# Dodobot.net
KiCad netlist of a schematic drawn in EAGLE
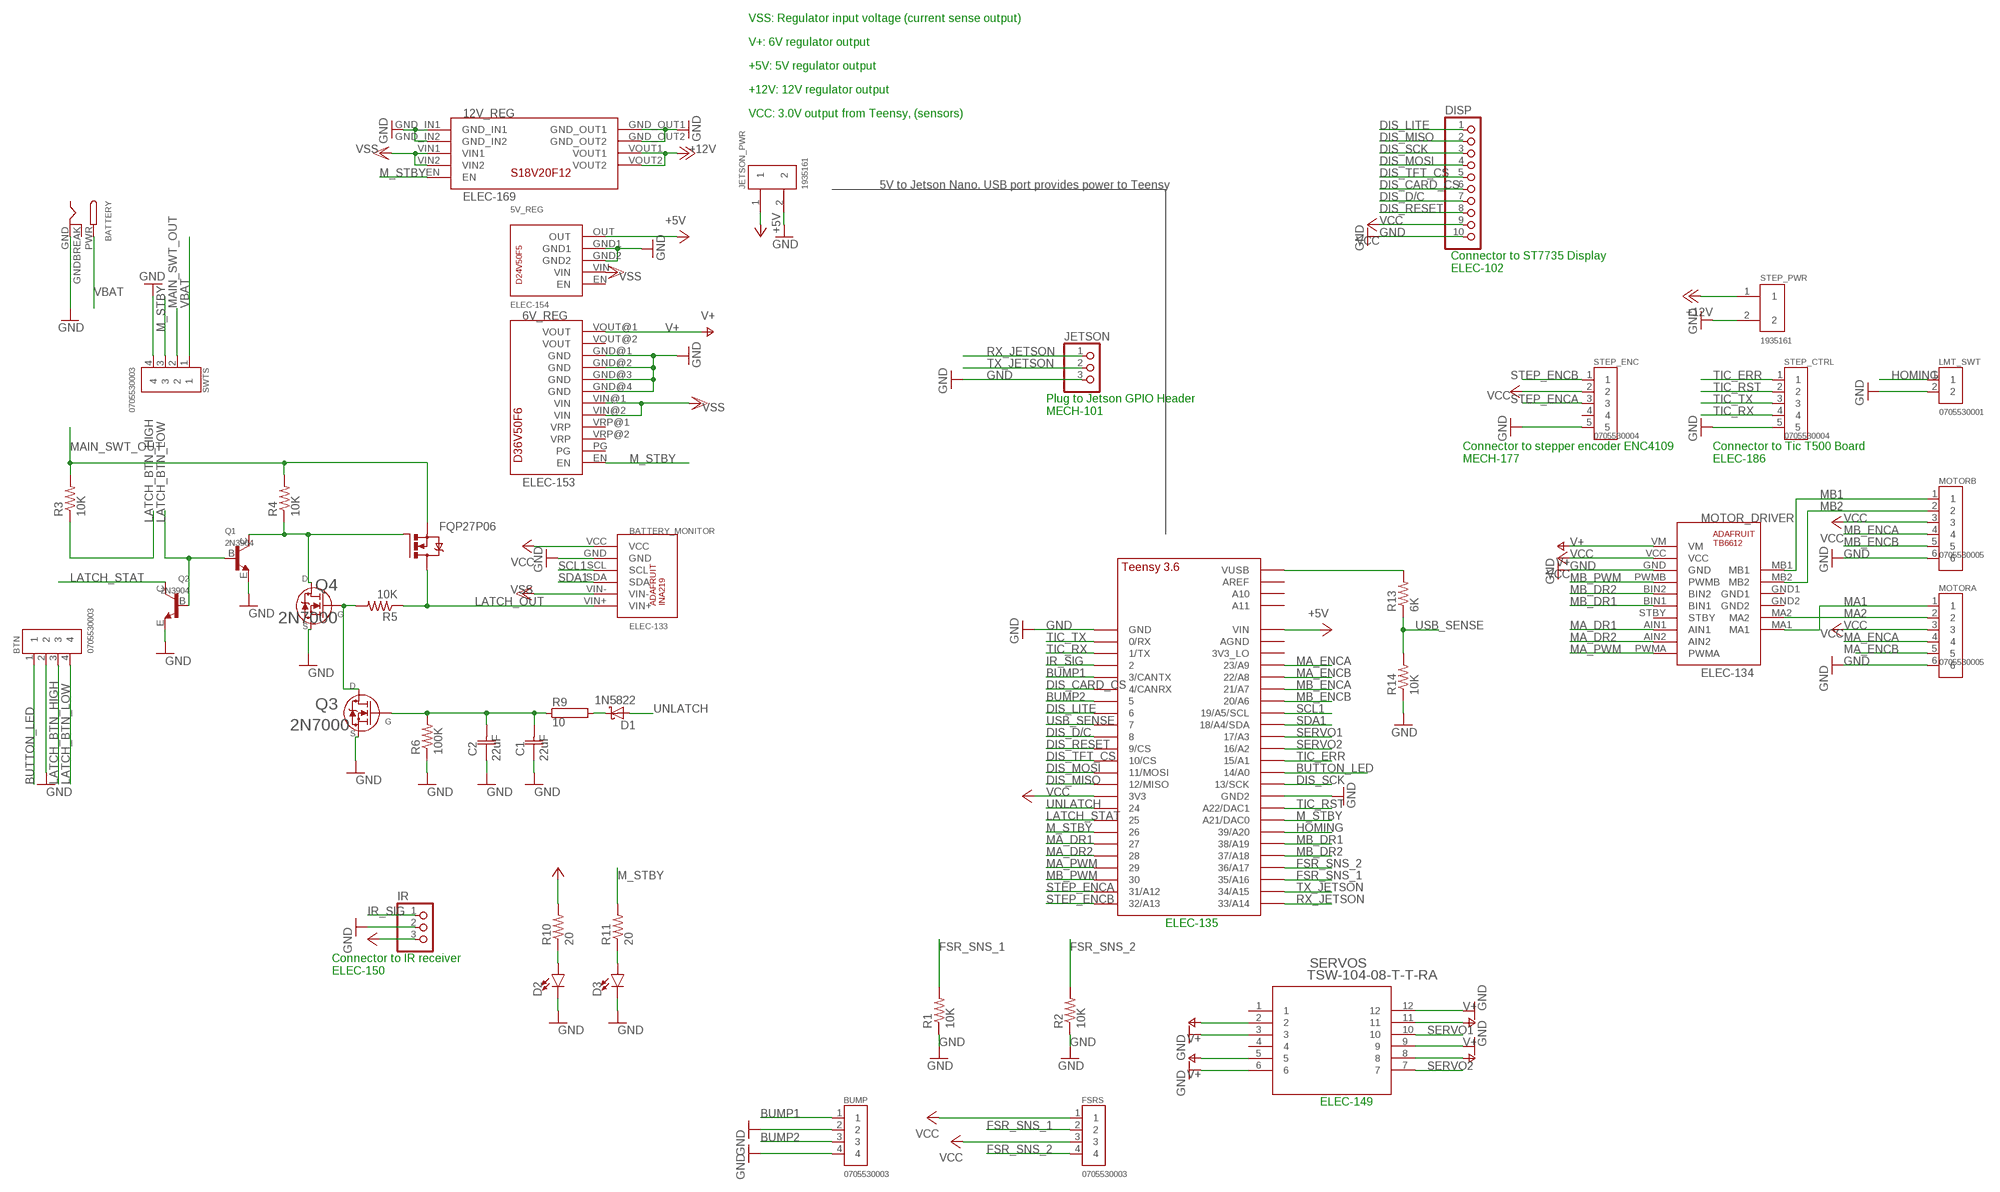
[diagram p0: schematic, sheet 1]

(export (version "E")
  (design (tool "Eeschema 10.0.6"))
  (components
    (comp (ref "5V_REG")
      (value "ELEC-154")
      (footprint "eagle-import:D24V50F5")
      (libsource (lib "eagle-import") (part "D24V50F5"))
    )
    (comp (ref "6V_REG")
      (value "ELEC-153")
      (footprint "eagle-import:D36V50FX")
      (libsource (lib "eagle-import") (part "D36V50FX"))
    )
    (comp (ref "12V_REG")
      (value "ELEC-169")
      (footprint "eagle-import:S18V20FX")
      (libsource (lib "eagle-import") (part "S18V20FX"))
    )
    (comp (ref "BATTERY")
      (value "DCBARRELPTH")
      (footprint "eagle-import:DCJACK_2MM_PTH")
      (libsource (lib "eagle-import") (part "DCBARRELPTH"))
    )
    (comp (ref "BATTERY_MONITOR")
      (value "ELEC-133")
      (footprint "eagle-import:INA219")
      (libsource (lib "eagle-import") (part "INA219"))
    )
    (comp (ref "BTN")
      (value "0705530003")
      (footprint "eagle-import:MOLEX_0705530003")
      (fields (field (name "DIGI-KEY_PART_NUMBER") "WM4902-ND") (field (name "MF") "Molex"))
      (libsource (lib "eagle-import") (part "0705530003"))
    )
    (comp (ref "BUMP")
      (value "0705530003")
      (footprint "eagle-import:MOLEX_0705530003")
      (fields (field (name "DIGI-KEY_PART_NUMBER") "WM4902-ND") (field (name "MF") "Molex"))
      (libsource (lib "eagle-import") (part "0705530003"))
    )
    (comp (ref "C1")
      (value "22uF")
      (footprint "eagle-import:CAP_R4525B")
      (fields (field (name "MANUFACTURER_PART_NUMBER") "FK24X5R0J226M"))
      (libsource (lib "eagle-import") (part "FK24X5R0J226M"))
    )
    (comp (ref "C2")
      (value "22uF")
      (footprint "eagle-import:CAP_R4525B")
      (fields (field (name "MANUFACTURER_PART_NUMBER") "FK24X5R0J226M"))
      (libsource (lib "eagle-import") (part "FK24X5R0J226M"))
    )
    (comp (ref "D1")
      (value "1N5822")
      (footprint "eagle-import:DIOAD2120W130L950D530P")
      (fields (field (name "DIGI-KEY_PART_NUMBER") "1N5822FSCT-ND") (field (name "MF") "ON Semiconductor"))
      (libsource (lib "eagle-import") (part "1N5822"))
    )
    (comp (ref "D2")
      (value "LED1206")
      (footprint "eagle-import:LED-1206")
      (libsource (lib "eagle-import") (part "LED1206"))
    )
    (comp (ref "D3")
      (value "LED1206")
      (footprint "eagle-import:LED-1206")
      (libsource (lib "eagle-import") (part "LED1206"))
    )
    (comp (ref "DISP")
      (value "PINHD-1X10")
      (footprint "eagle-import:1X10")
      (libsource (lib "eagle-import") (part "PINHD-1X10"))
    )
    (comp (ref "FQP27P06")
      (value "IRF530")
      (footprint "eagle-import:TO220BV")
      (fields (field (name "MF") "Vishay Siliconix"))
      (libsource (lib "eagle-import") (part "IRF530"))
    )
    (comp (ref "FSRS")
      (value "0705530003")
      (footprint "eagle-import:MOLEX_0705530003")
      (fields (field (name "DIGI-KEY_PART_NUMBER") "WM4902-ND") (field (name "MF") "Molex"))
      (libsource (lib "eagle-import") (part "0705530003"))
    )
    (comp (ref "IR")
      (value "PINHD-1X3")
      (footprint "eagle-import:1X03")
      (libsource (lib "eagle-import") (part "PINHD-1X3"))
    )
    (comp (ref "JETSON")
      (value "PINHD-1X3")
      (footprint "eagle-import:1X03")
      (libsource (lib "eagle-import") (part "PINHD-1X3"))
    )
    (comp (ref "JETSON_PWR")
      (value "1935161")
      (footprint "eagle-import:PHOENIX_1935161")
      (fields (field (name "DIGI-KEY_PART_NUMBER") "277-1667-ND") (field (name "MF") "Phoenix Contact"))
      (libsource (lib "eagle-import") (part "1935161"))
    )
    (comp (ref "LMT_SWT")
      (value "0705530001")
      (footprint "eagle-import:MOLEX_0705530001")
      (libsource (lib "eagle-import") (part "0705530001"))
    )
    (comp (ref "MOTORA")
      (value "0705530005")
      (footprint "eagle-import:MOLEX_0705530005")
      (libsource (lib "eagle-import") (part "0705530005"))
    )
    (comp (ref "MOTORB")
      (value "0705530005")
      (footprint "eagle-import:MOLEX_0705530005")
      (libsource (lib "eagle-import") (part "0705530005"))
    )
    (comp (ref "MOTOR_DRIVER")
      (value "ELEC-134")
      (footprint "eagle-import:ADAFRUIT_TB6612")
      (libsource (lib "eagle-import") (part "ADAFRUIT_TB6612"))
    )
    (comp (ref "Q1")
      (value "2N3904")
      (footprint "eagle-import:TO92")
      (libsource (lib "eagle-import") (part "2N3904"))
    )
    (comp (ref "Q2")
      (value "2N3904")
      (footprint "eagle-import:TO92")
      (libsource (lib "eagle-import") (part "2N3904"))
    )
    (comp (ref "Q3")
      (value "2N7000")
      (footprint "eagle-import:TO-92")
      (libsource (lib "eagle-import") (part "2N7000"))
    )
    (comp (ref "Q4")
      (value "2N7000")
      (footprint "eagle-import:TO-92")
      (libsource (lib "eagle-import") (part "2N7000"))
    )
    (comp (ref "R1")
      (value "10K")
      (footprint "eagle-import:RES_0805")
      (fields
        (field (name "DIGIKEY_PART_NUMBER") "541-0.0ATR-ND")
        (field (name "MANUFACTURER") "Vishay Dale")
        (field (name "MPN") "CRCW08050000Z0EA")
        (field (name "CREATED_BY") "PCBLayout.com")
      )
      (libsource (lib "eagle-import") (part "CRCW08050000Z0EA"))
    )
    (comp (ref "R2")
      (value "10K")
      (footprint "eagle-import:RES_0805")
      (fields
        (field (name "DIGIKEY_PART_NUMBER") "541-0.0ATR-ND")
        (field (name "MANUFACTURER") "Vishay Dale")
        (field (name "MPN") "CRCW08050000Z0EA")
        (field (name "CREATED_BY") "PCBLayout.com")
      )
      (libsource (lib "eagle-import") (part "CRCW08050000Z0EA"))
    )
    (comp (ref "R3")
      (value "10K")
      (footprint "eagle-import:RES_0805")
      (fields
        (field (name "DIGIKEY_PART_NUMBER") "541-0.0ATR-ND")
        (field (name "MANUFACTURER") "Vishay Dale")
        (field (name "MPN") "CRCW08050000Z0EA")
        (field (name "CREATED_BY") "PCBLayout.com")
      )
      (libsource (lib "eagle-import") (part "CRCW08050000Z0EA"))
    )
    (comp (ref "R4")
      (value "10K")
      (footprint "eagle-import:RES_0805")
      (fields
        (field (name "DIGIKEY_PART_NUMBER") "541-0.0ATR-ND")
        (field (name "MANUFACTURER") "Vishay Dale")
        (field (name "MPN") "CRCW08050000Z0EA")
        (field (name "CREATED_BY") "PCBLayout.com")
      )
      (libsource (lib "eagle-import") (part "CRCW08050000Z0EA"))
    )
    (comp (ref "R5")
      (value "10K")
      (footprint "eagle-import:RES_0805")
      (fields
        (field (name "DIGIKEY_PART_NUMBER") "541-0.0ATR-ND")
        (field (name "MANUFACTURER") "Vishay Dale")
        (field (name "MPN") "CRCW08050000Z0EA")
        (field (name "CREATED_BY") "PCBLayout.com")
      )
      (libsource (lib "eagle-import") (part "CRCW08050000Z0EA"))
    )
    (comp (ref "R6")
      (value "100K")
      (footprint "eagle-import:RES_0805")
      (fields
        (field (name "DIGIKEY_PART_NUMBER") "541-0.0ATR-ND")
        (field (name "MANUFACTURER") "Vishay Dale")
        (field (name "MPN") "CRCW08050000Z0EA")
        (field (name "CREATED_BY") "PCBLayout.com")
      )
      (libsource (lib "eagle-import") (part "CRCW08050000Z0EA"))
    )
    (comp (ref "R9")
      (value "10")
      (footprint "eagle-import:HPS58")
      (libsource (lib "eagle-import") (part "RHPS58"))
    )
    (comp (ref "R10")
      (value "20")
      (footprint "eagle-import:RES_1206")
      (fields
        (field (name "DIGIKEY_PART_NUMBER") "WSLP-.05TR-ND")
        (field (name "MANUFACTURER") "Vishay Dale")
        (field (name "MPN") "WSLP1206R0500FEA")
        (field (name "CREATED_BY") "PCBLayout.com")
      )
      (libsource (lib "eagle-import") (part "WSLP1206R0500FEA"))
    )
    (comp (ref "R11")
      (value "20")
      (footprint "eagle-import:RES_1206")
      (fields
        (field (name "DIGIKEY_PART_NUMBER") "WSLP-.05TR-ND")
        (field (name "MANUFACTURER") "Vishay Dale")
        (field (name "MPN") "WSLP1206R0500FEA")
        (field (name "CREATED_BY") "PCBLayout.com")
      )
      (libsource (lib "eagle-import") (part "WSLP1206R0500FEA"))
    )
    (comp (ref "R13")
      (value "6K")
      (footprint "eagle-import:RES_0805")
      (fields
        (field (name "DIGIKEY_PART_NUMBER") "541-0.0ATR-ND")
        (field (name "MANUFACTURER") "Vishay Dale")
        (field (name "MPN") "CRCW08050000Z0EA")
        (field (name "CREATED_BY") "PCBLayout.com")
      )
      (libsource (lib "eagle-import") (part "CRCW08050000Z0EA"))
    )
    (comp (ref "R14")
      (value "10K")
      (footprint "eagle-import:RES_0805")
      (fields
        (field (name "DIGIKEY_PART_NUMBER") "541-0.0ATR-ND")
        (field (name "MANUFACTURER") "Vishay Dale")
        (field (name "MPN") "CRCW08050000Z0EA")
        (field (name "CREATED_BY") "PCBLayout.com")
      )
      (libsource (lib "eagle-import") (part "CRCW08050000Z0EA"))
    )
    (comp (ref "SERVOS")
      (value "TSW-104-08-T-T-RA")
      (footprint "eagle-import:TSW-104-08-T-T-RA_SAI")
      (libsource (lib "eagle-import") (part "TSW-104-08-T-T-RA"))
    )
    (comp (ref "STEP_CTRL")
      (value "0705530004")
      (footprint "eagle-import:MOLEX_0705530004")
      (libsource (lib "eagle-import") (part "0705530004"))
    )
    (comp (ref "STEP_ENC")
      (value "0705530004")
      (footprint "eagle-import:MOLEX_0705530004")
      (libsource (lib "eagle-import") (part "0705530004"))
    )
    (comp (ref "STEP_PWR")
      (value "1935161")
      (footprint "eagle-import:PHOENIX_1935161")
      (fields (field (name "DIGI-KEY_PART_NUMBER") "277-1667-ND") (field (name "MF") "Phoenix Contact"))
      (libsource (lib "eagle-import") (part "1935161"))
    )
    (comp (ref "SWTS")
      (value "0705530003")
      (footprint "eagle-import:MOLEX_0705530003")
      (fields (field (name "DIGI-KEY_PART_NUMBER") "WM4902-ND") (field (name "MF") "Molex"))
      (libsource (lib "eagle-import") (part "0705530003"))
    )
    (comp (ref "U$1")
      (value "TEENSY_3.5/3.6_BASIC")
      (footprint "eagle-import:TEENSY_3.5_3.6_BASIC")
      (libsource (lib "eagle-import") (part "TEENSY_3.5/3.6_BASIC"))
    )
  )
  (nets
    (net (code "1") (name "+5V") (class "Default")
      (node (ref "5V_REG") (pin "OUT") (pinfunction "OUT_OUT") (pintype "bidirectional"))
      (node (ref "JETSON_PWR") (pin "1") (pinfunction "1_1") (pintype "passive"))
      (node (ref "U$1") (pin "VIN") (pinfunction "VIN_VIN") (pintype "bidirectional"))
    )
    (net (code "2") (name "+12V") (class "Default")
      (node (ref "12V_REG") (pin "VOUT1") (pinfunction "VOUT1_VOUT1") (pintype "bidirectional"))
      (node (ref "12V_REG") (pin "VOUT2") (pinfunction "VOUT2_VOUT2") (pintype "bidirectional"))
      (node (ref "STEP_PWR") (pin "1") (pinfunction "1_1") (pintype "passive"))
    )
    (net (code "3") (name "/BUMP1") (class "Default")
      (node (ref "BUMP") (pin "1") (pinfunction "1_1") (pintype "passive"))
      (node (ref "U$1") (pin "3/CANTX") (pinfunction "3/CANTX_3/CANTX") (pintype "bidirectional"))
    )
    (net (code "4") (name "/BUMP2") (class "Default")
      (node (ref "BUMP") (pin "3") (pinfunction "3_3") (pintype "passive"))
      (node (ref "U$1") (pin "5") (pinfunction "5_5") (pintype "bidirectional"))
    )
    (net (code "5") (name "/BUTTON_LED") (class "Default")
      (node (ref "BTN") (pin "1") (pinfunction "1_1") (pintype "passive"))
      (node (ref "U$1") (pin "14/A0") (pinfunction "14/A0_14/A0") (pintype "bidirectional"))
    )
    (net (code "6") (name "/DIS_CARD_CS") (class "Default")
      (node (ref "DISP") (pin "6") (pinfunction "6_6") (pintype "passive"))
      (node (ref "U$1") (pin "4/CANRX") (pinfunction "4/CANRX_4/CANRX") (pintype "bidirectional"))
    )
    (net (code "7") (name "/DIS_D{slash}C") (class "Default")
      (node (ref "DISP") (pin "7") (pinfunction "7_7") (pintype "passive"))
      (node (ref "U$1") (pin "8") (pinfunction "8_8") (pintype "bidirectional"))
    )
    (net (code "8") (name "/DIS_LITE") (class "Default")
      (node (ref "DISP") (pin "1") (pinfunction "1_1") (pintype "passive"))
      (node (ref "U$1") (pin "6") (pinfunction "6_6") (pintype "bidirectional"))
    )
    (net (code "9") (name "/DIS_MISO") (class "Default")
      (node (ref "DISP") (pin "2") (pinfunction "2_2") (pintype "passive"))
      (node (ref "U$1") (pin "12/MISO") (pinfunction "12/MISO_12/MISO") (pintype "bidirectional"))
    )
    (net (code "10") (name "/DIS_MOSI") (class "Default")
      (node (ref "DISP") (pin "4") (pinfunction "4_4") (pintype "passive"))
      (node (ref "U$1") (pin "11/MOSI") (pinfunction "11/MOSI_11/MOSI") (pintype "bidirectional"))
    )
    (net (code "11") (name "/DIS_RESET") (class "Default")
      (node (ref "DISP") (pin "8") (pinfunction "8_8") (pintype "passive"))
      (node (ref "U$1") (pin "9/CS") (pinfunction "9/CS_9/CS") (pintype "bidirectional"))
    )
    (net (code "12") (name "/DIS_SCK") (class "Default")
      (node (ref "DISP") (pin "3") (pinfunction "3_3") (pintype "passive"))
      (node (ref "U$1") (pin "13/SCK") (pinfunction "13/SCK_13/SCK") (pintype "bidirectional"))
    )
    (net (code "13") (name "/DIS_TFT_CS") (class "Default")
      (node (ref "DISP") (pin "5") (pinfunction "5_5") (pintype "passive"))
      (node (ref "U$1") (pin "10/CS") (pinfunction "10/CS_10/CS") (pintype "bidirectional"))
    )
    (net (code "14") (name "/FSR_SNS_1") (class "Default")
      (node (ref "FSRS") (pin "2") (pinfunction "2_2") (pintype "passive"))
      (node (ref "R1") (pin "2") (pinfunction "2_2") (pintype "passive"))
      (node (ref "U$1") (pin "35/A16") (pinfunction "35/A16_35/A16") (pintype "bidirectional"))
    )
    (net (code "15") (name "/FSR_SNS_2") (class "Default")
      (node (ref "FSRS") (pin "4") (pinfunction "4_4") (pintype "passive"))
      (node (ref "R2") (pin "2") (pinfunction "2_2") (pintype "passive"))
      (node (ref "U$1") (pin "36/A17") (pinfunction "36/A17_36/A17") (pintype "bidirectional"))
    )
    (net (code "16") (name "/GNDBREAK") (class "Default")
      (node (ref "BATTERY") (pin "GNDBREAK") (pinfunction "GNDBREAK_GNDBREAK") (pintype "power_in"))
    )
    (net (code "17") (name "/HOMING") (class "Default")
      (node (ref "LMT_SWT") (pin "1") (pinfunction "1_1") (pintype "passive"))
      (node (ref "U$1") (pin "39/A20") (pinfunction "39/A20_39/A20") (pintype "bidirectional"))
    )
    (net (code "18") (name "/IR_SIG") (class "Default")
      (node (ref "IR") (pin "1") (pinfunction "1_1") (pintype "passive"))
      (node (ref "U$1") (pin "2") (pinfunction "2_2") (pintype "bidirectional"))
    )
    (net (code "19") (name "/LATCH_BTN_HIGH") (class "Default")
      (node (ref "BTN") (pin "3") (pinfunction "3_3") (pintype "passive"))
      (node (ref "R3") (pin "1") (pinfunction "1_1") (pintype "passive"))
    )
    (net (code "20") (name "/LATCH_BTN_LOW") (class "Default")
      (node (ref "BTN") (pin "4") (pinfunction "4_4") (pintype "passive"))
      (node (ref "Q1") (pin "B") (pinfunction "B_B") (pintype "passive"))
      (node (ref "Q2") (pin "B") (pinfunction "B_B") (pintype "passive"))
    )
    (net (code "21") (name "/LATCH_OUT") (class "Default")
      (node (ref "BATTERY_MONITOR") (pin "VIN+") (pinfunction "VIN+_VIN+") (pintype "bidirectional"))
      (node (ref "FQP27P06") (pin "D") (pinfunction "D_D") (pintype "passive"))
      (node (ref "R5") (pin "1") (pinfunction "1_1") (pintype "passive"))
    )
    (net (code "22") (name "/LATCH_STAT") (class "Default")
      (node (ref "Q2") (pin "C") (pinfunction "C_C") (pintype "passive"))
      (node (ref "U$1") (pin "25") (pinfunction "25_25") (pintype "bidirectional"))
    )
    (net (code "23") (name "/MA1") (class "Default")
      (node (ref "MOTORA") (pin "1") (pinfunction "1_1") (pintype "passive"))
      (node (ref "MOTOR_DRIVER") (pin "MA1") (pinfunction "MA1_MA1") (pintype "bidirectional"))
    )
    (net (code "24") (name "/MA2") (class "Default")
      (node (ref "MOTORA") (pin "2") (pinfunction "2_2") (pintype "passive"))
      (node (ref "MOTOR_DRIVER") (pin "MA2") (pinfunction "MA2_MA2") (pintype "bidirectional"))
    )
    (net (code "25") (name "/MAIN_SWT_OUT") (class "Default")
      (node (ref "FQP27P06") (pin "S") (pinfunction "S_S") (pintype "passive"))
      (node (ref "R3") (pin "2") (pinfunction "2_2") (pintype "passive"))
      (node (ref "R4") (pin "2") (pinfunction "2_2") (pintype "passive"))
      (node (ref "SWTS") (pin "2") (pinfunction "2_2") (pintype "passive"))
    )
    (net (code "26") (name "/MA_DR1") (class "Default")
      (node (ref "MOTOR_DRIVER") (pin "AIN1") (pinfunction "AIN1_AIN1") (pintype "bidirectional"))
      (node (ref "U$1") (pin "27") (pinfunction "27_27") (pintype "bidirectional"))
    )
    (net (code "27") (name "/MA_DR2") (class "Default")
      (node (ref "MOTOR_DRIVER") (pin "AIN2") (pinfunction "AIN2_AIN2") (pintype "bidirectional"))
      (node (ref "U$1") (pin "28") (pinfunction "28_28") (pintype "bidirectional"))
    )
    (net (code "28") (name "/MA_ENCA") (class "Default")
      (node (ref "MOTORA") (pin "4") (pinfunction "4_4") (pintype "passive"))
      (node (ref "U$1") (pin "23/A9") (pinfunction "23/A9_23/A9") (pintype "bidirectional"))
    )
    (net (code "29") (name "/MA_ENCB") (class "Default")
      (node (ref "MOTORA") (pin "5") (pinfunction "5_5") (pintype "passive"))
      (node (ref "U$1") (pin "22/A8") (pinfunction "22/A8_22/A8") (pintype "bidirectional"))
    )
    (net (code "30") (name "/MA_PWM") (class "Default")
      (node (ref "MOTOR_DRIVER") (pin "PWMA") (pinfunction "PWMA_PWMA") (pintype "bidirectional"))
      (node (ref "U$1") (pin "29") (pinfunction "29_29") (pintype "bidirectional"))
    )
    (net (code "31") (name "/MB1") (class "Default")
      (node (ref "MOTORB") (pin "1") (pinfunction "1_1") (pintype "passive"))
      (node (ref "MOTOR_DRIVER") (pin "MB1") (pinfunction "MB1_MB1") (pintype "bidirectional"))
    )
    (net (code "32") (name "/MB2") (class "Default")
      (node (ref "MOTORB") (pin "2") (pinfunction "2_2") (pintype "passive"))
      (node (ref "MOTOR_DRIVER") (pin "MB2") (pinfunction "MB2_MB2") (pintype "bidirectional"))
    )
    (net (code "33") (name "/MB_DR1") (class "Default")
      (node (ref "MOTOR_DRIVER") (pin "BIN1") (pinfunction "BIN1_BIN1") (pintype "bidirectional"))
      (node (ref "U$1") (pin "38/A19") (pinfunction "38/A19_38/A19") (pintype "bidirectional"))
    )
    (net (code "34") (name "/MB_DR2") (class "Default")
      (node (ref "MOTOR_DRIVER") (pin "BIN2") (pinfunction "BIN2_BIN2") (pintype "bidirectional"))
      (node (ref "U$1") (pin "37/A18") (pinfunction "37/A18_37/A18") (pintype "bidirectional"))
    )
    (net (code "35") (name "/MB_ENCA") (class "Default")
      (node (ref "MOTORB") (pin "4") (pinfunction "4_4") (pintype "passive"))
      (node (ref "U$1") (pin "21/A7") (pinfunction "21/A7_21/A7") (pintype "bidirectional"))
    )
    (net (code "36") (name "/MB_ENCB") (class "Default")
      (node (ref "MOTORB") (pin "5") (pinfunction "5_5") (pintype "passive"))
      (node (ref "U$1") (pin "20/A6") (pinfunction "20/A6_20/A6") (pintype "bidirectional"))
    )
    (net (code "37") (name "/MB_PWM") (class "Default")
      (node (ref "MOTOR_DRIVER") (pin "PWMB") (pinfunction "PWMB_PWMB") (pintype "bidirectional"))
      (node (ref "U$1") (pin "30") (pinfunction "30_30") (pintype "bidirectional"))
    )
    (net (code "38") (name "/M_STBY") (class "Default")
      (node (ref "12V_REG") (pin "EN") (pinfunction "EN_EN") (pintype "bidirectional"))
      (node (ref "6V_REG") (pin "EN") (pinfunction "EN_EN") (pintype "bidirectional"))
      (node (ref "R11") (pin "2") (pinfunction "2_2") (pintype "passive"))
      (node (ref "SWTS") (pin "3") (pinfunction "3_3") (pintype "passive"))
      (node (ref "U$1") (pin "21/DAC0") (pinfunction "A21/DAC0_21/DAC0") (pintype "bidirectional"))
      (node (ref "U$1") (pin "26") (pinfunction "26_26") (pintype "bidirectional"))
    )
    (net (code "39") (name "/RX_JETSON") (class "Default")
      (node (ref "JETSON") (pin "1") (pinfunction "1_1") (pintype "passive"))
      (node (ref "U$1") (pin "33/A14") (pinfunction "33/A14_33/A14") (pintype "bidirectional"))
    )
    (net (code "40") (name "/SCL1") (class "Default")
      (node (ref "BATTERY_MONITOR") (pin "SCL") (pinfunction "SCL_SCL") (pintype "bidirectional"))
      (node (ref "U$1") (pin "19/A5/SCL") (pinfunction "19/A5/SCL_19/A5/SCL") (pintype "bidirectional"))
    )
    (net (code "41") (name "/SDA1") (class "Default")
      (node (ref "BATTERY_MONITOR") (pin "SDA") (pinfunction "SDA_SDA") (pintype "bidirectional"))
      (node (ref "U$1") (pin "18/A4/SDA") (pinfunction "18/A4/SDA_18/A4/SDA") (pintype "bidirectional"))
    )
    (net (code "42") (name "/SERVO1") (class "Default")
      (node (ref "SERVOS") (pin "10") (pinfunction "10_10") (pintype "passive"))
      (node (ref "U$1") (pin "17/A3") (pinfunction "17/A3_17/A3") (pintype "bidirectional"))
    )
    (net (code "43") (name "/SERVO2") (class "Default")
      (node (ref "SERVOS") (pin "7") (pinfunction "7_7") (pintype "passive"))
      (node (ref "U$1") (pin "16/A2") (pinfunction "16/A2_16/A2") (pintype "bidirectional"))
    )
    (net (code "44") (name "/STEP_ENCA") (class "Default")
      (node (ref "STEP_ENC") (pin "3") (pinfunction "3_3") (pintype "passive"))
      (node (ref "U$1") (pin "31/A12") (pinfunction "31/A12_31/A12") (pintype "bidirectional"))
    )
    (net (code "45") (name "/STEP_ENCB") (class "Default")
      (node (ref "STEP_ENC") (pin "1") (pinfunction "1_1") (pintype "passive"))
      (node (ref "U$1") (pin "32/A13") (pinfunction "32/A13_32/A13") (pintype "bidirectional"))
    )
    (net (code "46") (name "/TIC_ERR") (class "Default")
      (node (ref "STEP_CTRL") (pin "1") (pinfunction "1_1") (pintype "passive"))
      (node (ref "U$1") (pin "15/A1") (pinfunction "15/A1_15/A1") (pintype "bidirectional"))
    )
    (net (code "47") (name "/TIC_RST") (class "Default")
      (node (ref "STEP_CTRL") (pin "2") (pinfunction "2_2") (pintype "passive"))
      (node (ref "U$1") (pin "A22/DAC1") (pinfunction "A22/DAC1_A22/DAC1") (pintype "bidirectional"))
    )
    (net (code "48") (name "/TIC_RX") (class "Default")
      (node (ref "STEP_CTRL") (pin "4") (pinfunction "4_4") (pintype "passive"))
      (node (ref "U$1") (pin "1/TX") (pinfunction "1/TX_1/TX") (pintype "bidirectional"))
    )
    (net (code "49") (name "/TIC_TX") (class "Default")
      (node (ref "STEP_CTRL") (pin "3") (pinfunction "3_3") (pintype "passive"))
      (node (ref "U$1") (pin "0/RX") (pinfunction "0/RX_0/RX") (pintype "bidirectional"))
    )
    (net (code "50") (name "/TX_JETSON") (class "Default")
      (node (ref "JETSON") (pin "2") (pinfunction "2_2") (pintype "passive"))
      (node (ref "U$1") (pin "34/A15") (pinfunction "34/A15_34/A15") (pintype "bidirectional"))
    )
    (net (code "51") (name "/UNLATCH") (class "Default")
      (node (ref "D1") (pin "A") (pinfunction "A_A") (pintype "passive"))
      (node (ref "U$1") (pin "24") (pinfunction "24_24") (pintype "bidirectional"))
    )
    (net (code "52") (name "/USB_SENSE") (class "Default")
      (node (ref "R13") (pin "1") (pinfunction "1_1") (pintype "passive"))
      (node (ref "R14") (pin "2") (pinfunction "2_2") (pintype "passive"))
      (node (ref "U$1") (pin "7") (pinfunction "7_7") (pintype "bidirectional"))
    )
    (net (code "53") (name "/VBAT") (class "Default")
      (node (ref "BATTERY") (pin "PWR") (pinfunction "PWR_PWR") (pintype "power_in"))
      (node (ref "SWTS") (pin "1") (pinfunction "1_1") (pintype "passive"))
    )
    (net (code "54") (name "GND") (class "Default")
      (node (ref "12V_REG") (pin "GND_IN1") (pinfunction "GND_IN1_GND_IN1") (pintype "bidirectional"))
      (node (ref "12V_REG") (pin "GND_IN2") (pinfunction "GND_IN2_GND_IN2") (pintype "bidirectional"))
      (node (ref "12V_REG") (pin "GND_OUT1") (pinfunction "GND_OUT1_GND_OUT1") (pintype "bidirectional"))
      (node (ref "12V_REG") (pin "GND_OUT2") (pinfunction "GND_OUT2_GND_OUT2") (pintype "bidirectional"))
      (node (ref "5V_REG") (pin "GND1") (pinfunction "GND1_GND1") (pintype "bidirectional"))
      (node (ref "5V_REG") (pin "GND2") (pinfunction "GND2_GND2") (pintype "bidirectional"))
      (node (ref "6V_REG") (pin "GND@1") (pinfunction "GND_GND@1") (pintype "bidirectional"))
      (node (ref "6V_REG") (pin "GND@2") (pinfunction "GND_GND@2") (pintype "bidirectional"))
      (node (ref "6V_REG") (pin "GND@3") (pinfunction "GND_GND@3") (pintype "bidirectional"))
      (node (ref "6V_REG") (pin "GND@4") (pinfunction "GND_GND@4") (pintype "bidirectional"))
      (node (ref "BATTERY") (pin "GND") (pinfunction "GND_GND") (pintype "power_in"))
      (node (ref "BATTERY_MONITOR") (pin "GND") (pinfunction "GND_GND") (pintype "bidirectional"))
      (node (ref "BTN") (pin "2") (pinfunction "2_2") (pintype "passive"))
      (node (ref "BUMP") (pin "2") (pinfunction "2_2") (pintype "passive"))
      (node (ref "BUMP") (pin "4") (pinfunction "4_4") (pintype "passive"))
      (node (ref "C1") (pin "1") (pinfunction "1_1") (pintype "passive"))
      (node (ref "C2") (pin "1") (pinfunction "1_1") (pintype "passive"))
      (node (ref "D2") (pin "C") (pinfunction "C_C") (pintype "passive"))
      (node (ref "D3") (pin "C") (pinfunction "C_C") (pintype "passive"))
      (node (ref "DISP") (pin "10") (pinfunction "10_10") (pintype "passive"))
      (node (ref "IR") (pin "2") (pinfunction "2_2") (pintype "passive"))
      (node (ref "JETSON") (pin "3") (pinfunction "3_3") (pintype "passive"))
      (node (ref "JETSON_PWR") (pin "2") (pinfunction "2_2") (pintype "passive"))
      (node (ref "LMT_SWT") (pin "2") (pinfunction "2_2") (pintype "passive"))
      (node (ref "MOTORA") (pin "6") (pinfunction "6_6") (pintype "passive"))
      (node (ref "MOTORB") (pin "6") (pinfunction "6_6") (pintype "passive"))
      (node (ref "MOTOR_DRIVER") (pin "GND") (pinfunction "GND_GND") (pintype "bidirectional"))
      (node (ref "Q1") (pin "E") (pinfunction "E_E") (pintype "passive"))
      (node (ref "Q2") (pin "E") (pinfunction "E_E") (pintype "passive"))
      (node (ref "Q3") (pin "1") (pinfunction "3_1") (pintype "passive"))
      (node (ref "Q4") (pin "1") (pinfunction "3_1") (pintype "passive"))
      (node (ref "R1") (pin "1") (pinfunction "1_1") (pintype "passive"))
      (node (ref "R14") (pin "1") (pinfunction "1_1") (pintype "passive"))
      (node (ref "R2") (pin "1") (pinfunction "1_1") (pintype "passive"))
      (node (ref "R6") (pin "1") (pinfunction "1_1") (pintype "passive"))
      (node (ref "SERVOS") (pin "12") (pinfunction "12_12") (pintype "passive"))
      (node (ref "SERVOS") (pin "3") (pinfunction "3_3") (pintype "passive"))
      (node (ref "SERVOS") (pin "6") (pinfunction "6_6") (pintype "passive"))
      (node (ref "SERVOS") (pin "9") (pinfunction "9_9") (pintype "passive"))
      (node (ref "STEP_CTRL") (pin "5") (pinfunction "5_5") (pintype "passive"))
      (node (ref "STEP_ENC") (pin "5") (pinfunction "5_5") (pintype "passive"))
      (node (ref "STEP_PWR") (pin "2") (pinfunction "2_2") (pintype "passive"))
      (node (ref "SWTS") (pin "4") (pinfunction "4_4") (pintype "passive"))
      (node (ref "U$1") (pin "GND") (pinfunction "GND_GND") (pintype "bidirectional"))
      (node (ref "U$1") (pin "GND2") (pinfunction "GND2_GND2") (pintype "bidirectional"))
    )
    (net (code "55") (name "Net-(D1-PadC)") (class "Default")
      (node (ref "D1") (pin "C") (pinfunction "C_C") (pintype "passive"))
      (node (ref "R9") (pin "2") (pinfunction "2_2") (pintype "passive"))
    )
    (net (code "56") (name "Net-(D2-PadA)") (class "Default")
      (node (ref "D2") (pin "A") (pinfunction "A_A") (pintype "passive"))
      (node (ref "R10") (pin "1") (pinfunction "1_1") (pintype "passive"))
    )
    (net (code "57") (name "Net-(D3-PadA)") (class "Default")
      (node (ref "D3") (pin "A") (pinfunction "A_A") (pintype "passive"))
      (node (ref "R11") (pin "1") (pinfunction "1_1") (pintype "passive"))
    )
    (net (code "58") (name "Net-(Q3-1)") (class "Default")
      (node (ref "C1") (pin "2") (pinfunction "2_2") (pintype "passive"))
      (node (ref "C2") (pin "2") (pinfunction "2_2") (pintype "passive"))
      (node (ref "Q3") (pin "2") (pinfunction "1_2") (pintype "passive"))
      (node (ref "R6") (pin "2") (pinfunction "2_2") (pintype "passive"))
      (node (ref "R9") (pin "1") (pinfunction "1_1") (pintype "passive"))
    )
    (net (code "59") (name "Net-(Q3-2)") (class "Default")
      (node (ref "Q3") (pin "3") (pinfunction "2_3") (pintype "passive"))
      (node (ref "Q4") (pin "2") (pinfunction "1_2") (pintype "passive"))
      (node (ref "R5") (pin "2") (pinfunction "2_2") (pintype "passive"))
    )
    (net (code "60") (name "Net-(Q4-2)") (class "Default")
      (node (ref "FQP27P06") (pin "G") (pinfunction "G_G") (pintype "passive"))
      (node (ref "Q1") (pin "C") (pinfunction "C_C") (pintype "passive"))
      (node (ref "Q4") (pin "3") (pinfunction "2_3") (pintype "passive"))
      (node (ref "R4") (pin "1") (pinfunction "1_1") (pintype "passive"))
    )
    (net (code "61") (name "Net-(R13-Pad2)") (class "Default")
      (node (ref "R13") (pin "2") (pinfunction "2_2") (pintype "passive"))
      (node (ref "U$1") (pin "VUSB") (pinfunction "VUSB_VUSB") (pintype "bidirectional"))
    )
    (net (code "62") (name "V+") (class "Default")
      (node (ref "6V_REG") (pin "VOUT@1") (pinfunction "VOUT_VOUT@1") (pintype "bidirectional"))
      (node (ref "MOTOR_DRIVER") (pin "VM") (pinfunction "VM_VM") (pintype "bidirectional"))
      (node (ref "SERVOS") (pin "11") (pinfunction "11_11") (pintype "passive"))
      (node (ref "SERVOS") (pin "2") (pinfunction "2_2") (pintype "passive"))
      (node (ref "SERVOS") (pin "5") (pinfunction "5_5") (pintype "passive"))
      (node (ref "SERVOS") (pin "8") (pinfunction "8_8") (pintype "passive"))
    )
    (net (code "63") (name "VCC") (class "Default")
      (node (ref "BATTERY_MONITOR") (pin "VCC") (pinfunction "VCC_VCC") (pintype "bidirectional"))
      (node (ref "DISP") (pin "9") (pinfunction "9_9") (pintype "passive"))
      (node (ref "FSRS") (pin "1") (pinfunction "1_1") (pintype "passive"))
      (node (ref "FSRS") (pin "3") (pinfunction "3_3") (pintype "passive"))
      (node (ref "IR") (pin "3") (pinfunction "3_3") (pintype "passive"))
      (node (ref "MOTORA") (pin "3") (pinfunction "3_3") (pintype "passive"))
      (node (ref "MOTORB") (pin "3") (pinfunction "3_3") (pintype "passive"))
      (node (ref "MOTOR_DRIVER") (pin "VCC") (pinfunction "VCC_VCC") (pintype "bidirectional"))
      (node (ref "R10") (pin "2") (pinfunction "2_2") (pintype "passive"))
      (node (ref "STEP_ENC") (pin "2") (pinfunction "2_2") (pintype "passive"))
      (node (ref "U$1") (pin "3V3") (pinfunction "3V3_3V3") (pintype "bidirectional"))
    )
    (net (code "64") (name "VSS") (class "Default")
      (node (ref "12V_REG") (pin "VIN1") (pinfunction "VIN1_VIN1") (pintype "bidirectional"))
      (node (ref "12V_REG") (pin "VIN2") (pinfunction "VIN2_VIN2") (pintype "bidirectional"))
      (node (ref "5V_REG") (pin "VIN") (pinfunction "VIN_VIN") (pintype "bidirectional"))
      (node (ref "6V_REG") (pin "VIN@1") (pinfunction "VIN_VIN@1") (pintype "bidirectional"))
      (node (ref "6V_REG") (pin "VIN@2") (pinfunction "VIN_VIN@2") (pintype "bidirectional"))
      (node (ref "BATTERY_MONITOR") (pin "VIN-") (pinfunction "VIN-_VIN-") (pintype "bidirectional"))
    )
    (net (code "65") (name "unconnected-(5V_REG-PadEN)") (class "Default")
      (node (ref "5V_REG") (pin "EN") (pinfunction "EN_EN") (pintype "bidirectional"))
    )
    (net (code "66") (name "unconnected-(6V_REG-PadPG)") (class "Default")
      (node (ref "6V_REG") (pin "PG") (pinfunction "PG_PG") (pintype "bidirectional"))
    )
    (net (code "67") (name "unconnected-(6V_REG-VOUT-PadVOUT@2)") (class "Default")
      (node (ref "6V_REG") (pin "VOUT@2") (pinfunction "VOUT_VOUT@2") (pintype "bidirectional"))
    )
    (net (code "68") (name "unconnected-(6V_REG-VRP-PadVRP@1)") (class "Default")
      (node (ref "6V_REG") (pin "VRP@1") (pinfunction "VRP_VRP@1") (pintype "bidirectional"))
    )
    (net (code "69") (name "unconnected-(6V_REG-VRP-PadVRP@2)") (class "Default")
      (node (ref "6V_REG") (pin "VRP@2") (pinfunction "VRP_VRP@2") (pintype "bidirectional"))
    )
    (net (code "70") (name "unconnected-(MOTOR_DRIVER-PadGND1)") (class "Default")
      (node (ref "MOTOR_DRIVER") (pin "GND1") (pinfunction "GND1_GND1") (pintype "bidirectional"))
    )
    (net (code "71") (name "unconnected-(MOTOR_DRIVER-PadGND2)") (class "Default")
      (node (ref "MOTOR_DRIVER") (pin "GND2") (pinfunction "GND2_GND2") (pintype "bidirectional"))
    )
    (net (code "72") (name "unconnected-(MOTOR_DRIVER-PadSTBY)") (class "Default")
      (node (ref "MOTOR_DRIVER") (pin "STBY") (pinfunction "STBY_STBY") (pintype "bidirectional"))
    )
    (net (code "73") (name "unconnected-(SERVOS-Pad1)") (class "Default")
      (node (ref "SERVOS") (pin "1") (pinfunction "1_1") (pintype "passive"))
    )
    (net (code "74") (name "unconnected-(SERVOS-Pad4)") (class "Default")
      (node (ref "SERVOS") (pin "4") (pinfunction "4_4") (pintype "passive"))
    )
    (net (code "75") (name "unconnected-(STEP_ENC-Pad4)") (class "Default")
      (node (ref "STEP_ENC") (pin "4") (pinfunction "4_4") (pintype "passive"))
    )
    (net (code "76") (name "unconnected-(U$1-Pad3V3_LO)") (class "Default")
      (node (ref "U$1") (pin "3V3_LO") (pinfunction "3V3_LO_3V3_LO") (pintype "bidirectional"))
    )
    (net (code "77") (name "unconnected-(U$1-PadA10)") (class "Default")
      (node (ref "U$1") (pin "A10") (pinfunction "A10_A10") (pintype "bidirectional"))
    )
    (net (code "78") (name "unconnected-(U$1-PadA11)") (class "Default")
      (node (ref "U$1") (pin "A11") (pinfunction "A11_A11") (pintype "bidirectional"))
    )
    (net (code "79") (name "unconnected-(U$1-PadAGND)") (class "Default")
      (node (ref "U$1") (pin "AGND") (pinfunction "AGND_AGND") (pintype "bidirectional"))
    )
    (net (code "80") (name "unconnected-(U$1-PadAREF)") (class "Default")
      (node (ref "U$1") (pin "AREF") (pinfunction "AREF_AREF") (pintype "bidirectional"))
    )
  )
)
